# plp-cbot_2a.net
KiCad netlist of a schematic drawn in Altium Designer
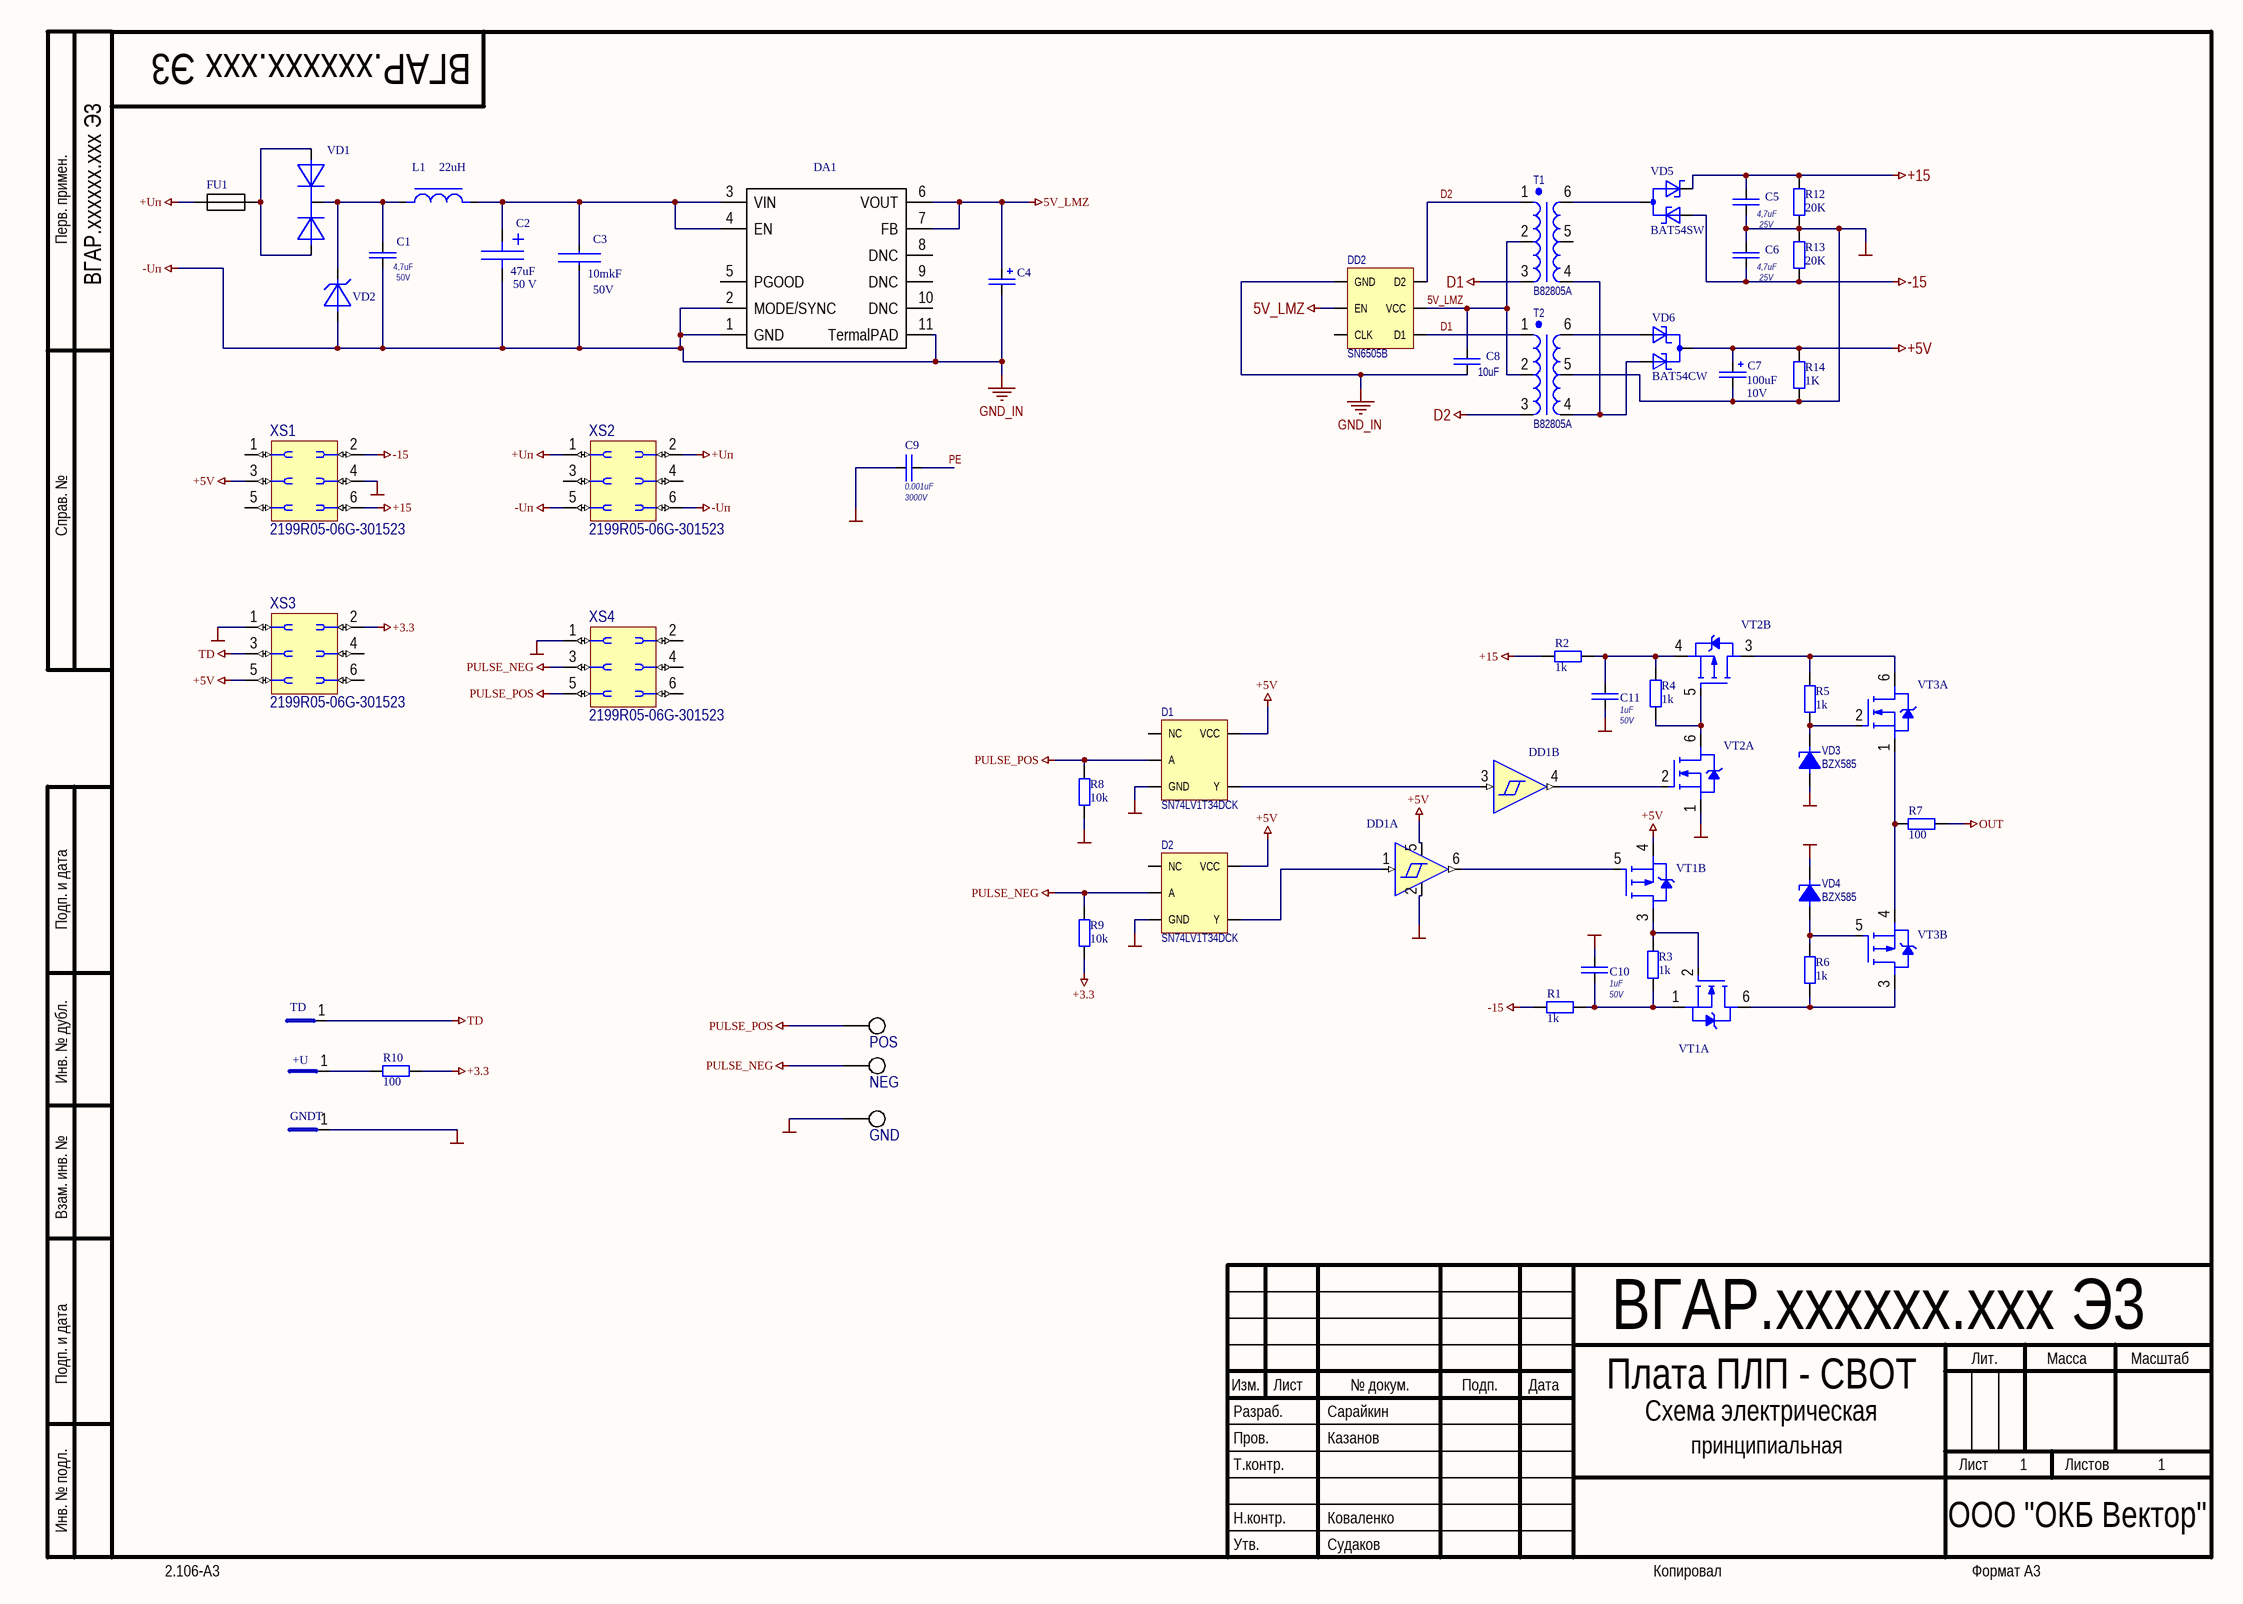
[diagram p0: plp-cbot_2a.SchDoc]

(export (version "E")
  (design (tool "Eeschema 10.0.6"))
  (components
    (comp (ref "+U")
      (value "smd_pin")
      (footprint "smd_pin")
      (libsource (lib "Board Level Debug Tools") (part "smd_pin"))
    )
    (comp (ref "C1")
      (value "4,7uF")
      (footprint "CAPC_0603(1608)X080L")
      (description "Конденсатор")
      (fields
        (field (name "MANUFACTURER") "Murata")
        (field (name "TOLERANCE") "±10%")
        (field (name "RATED DC VOLTAGE") "50V")
      )
      (libsource (lib "Chip Capacitor") (part "Capacitor Ceramic"))
    )
    (comp (ref "C2")
      (value "47uF")
      (footprint "CAPSM_D_M7878X54L")
      (description "Конденсатор")
      (fields
        (field (name "MANUFACTURER") "Panasonic")
        (field (name "TOLERANCE") "±20%")
        (field (name "RATED DC VOLTAGE") "50 V")
      )
      (libsource (lib "Panasonic Capacitor") (part "SMD 5.3XD6.3 ALUM 22uFx50V"))
    )
    (comp (ref "C3")
      (value "10mkF")
      (footprint "CAPC_1210(3225)X10L")
      (description "Capacitor Chip")
      (fields (field (name "ALTIUM_UNNAMED_1") "50V") (field (name "Comment") "CAPC_1210(3225)X10"))
      (libsource (lib "Yageo Chip Capacitor") (part "CAPC_1210(3225)X10"))
    )
    (comp (ref "C4")
      (value "~")
      (footprint "CAP_B3528X21N")
      (description "Конденсатор")
      (fields (field (name "MANUFACTURER") "Murata"))
      (libsource (lib "Chip Capacitor") (part "Capacitor Polarized"))
    )
    (comp (ref "C5")
      (value "4,7uF")
      (footprint "CAPC_0603(1608)X080L")
      (description "Конденсатор")
      (fields
        (field (name "MANUFACTURER") "Murata")
        (field (name "TOLERANCE") "±10%")
        (field (name "RATED DC VOLTAGE") "25V")
      )
      (libsource (lib "Chip Capacitor") (part "Capacitor Ceramic"))
    )
    (comp (ref "C6")
      (value "4,7uF")
      (footprint "CAPC_0603(1608)X080L")
      (description "Конденсатор")
      (fields
        (field (name "MANUFACTURER") "Murata")
        (field (name "TOLERANCE") "±10%")
        (field (name "RATED DC VOLTAGE") "25V")
      )
      (libsource (lib "Chip Capacitor") (part "Capacitor Ceramic"))
    )
    (comp (ref "C7")
      (value "100uF")
      (footprint "CAP_B3528X21N")
      (description "Конденсатор")
      (fields (field (name "MANUFACTURER") "Murata") (field (name "RATED DC VOLTAGE") "10V"))
      (libsource (lib "Chip Capacitor") (part "Capacitor Polarized"))
    )
    (comp (ref "C8")
      (value "10uF")
      (footprint "CAPC_0603(1608)X080L")
      (description "Конденсатор")
      (fields (field (name "MANUFACTURER") "Murata") (field (name "TOLERANCE") "±10%"))
      (libsource (lib "Chip Capacitor") (part "Capacitor Ceramic"))
    )
    (comp (ref "C9")
      (value "0.001uF")
      (footprint "CAPC_1812(4532)X16L")
      (description "Конденсатор")
      (fields
        (field (name "MANUFACTURER") "Murata")
        (field (name "PARTNUMBER") "0603 - 0,1 мкФ ± 10 % - 50 В - X7R")
        (field (name "RATED DC VOLTAGE") "3000V")
      )
      (libsource (lib "Chip Capacitor") (part "Capacitor Ceramic"))
    )
    (comp (ref "C10")
      (value "1uF")
      (footprint "CAPC_0603(1608)X080L")
      (description "Конденсатор")
      (fields
        (field (name "MANUFACTURER") "Murata")
        (field (name "PARTNUMBER") "GRM188R71C105KA12D - 0603 - 1 мкФ ± 10 % - 16 В - X7R")
        (field (name "RATED DC VOLTAGE") "50V")
      )
      (libsource (lib "Chip Capacitor") (part "0603 - X7R - 16V - 1uF"))
    )
    (comp (ref "C11")
      (value "1uF")
      (footprint "CAPC_0603(1608)X080L")
      (description "Конденсатор")
      (fields
        (field (name "MANUFACTURER") "Murata")
        (field (name "PARTNUMBER") "GRM188R71C105KA12D - 0603 - 1 мкФ ± 10 % - 16 В - X7R")
        (field (name "RATED DC VOLTAGE") "50V")
      )
      (libsource (lib "Chip Capacitor") (part "0603 - X7R - 16V - 1uF"))
    )
    (comp (ref "D1")
      (value "SN74LV1T34DCK")
      (footprint "SC70-5")
      (description "Single Buffer")
      (libsource (lib "ic-logic") (part "SN74LV1T34DCK"))
    )
    (comp (ref "D2")
      (value "SN74LV1T34DCK")
      (footprint "SC70-5")
      (description "Single Buffer")
      (libsource (lib "ic-logic") (part "SN74LV1T34DCK"))
    )
    (comp (ref "DA1")
      (value "LMZM23600")
      (footprint "MicroSIP")
      (description "Микросхема")
      (fields (field (name "MANUFACTURER") "Texas Instruments"))
      (libsource (lib "TI Power Mgt Switchmode Regulator") (part "LMZM23600"))
    )
    (comp (ref "DD1")
      (value "NC7WZ17P6X")
      (footprint "SC-70-6")
      (description "UHS Dual Buffer with Schmitt Trigger Inputs")
      (libsource (lib "Fairchild Logic") (part "NC7WZ17P6X"))
    )
    (comp (ref "DD2")
      (value "SN6505B")
      (footprint "SOT23-6")
      (description "Low-Noise 1-A Transformer Drivers for Isolated Power Supplies")
      (libsource (lib "ic-power-module") (part "SN6505A"))
    )
    (comp (ref "FU1")
      (value "MF-MSMF")
      (footprint "FU4532(1812)X06N")
      (description "Самовостанавливающийся предохранитель")
      (fields (field (name "MANUFACTURER") "Bourns") (field (name "PARTNUMBER") "MF-MSMF 010/60-2"))
      (libsource (lib "Bourns Chip Fuse") (part "MF-MSMF"))
    )
    (comp (ref "GND")
      (value "Testpoint_HS1mm")
      (footprint "TestPoint(1mm_HS)")
      (libsource (lib "connector") (part "Testpoint_HS1mm"))
    )
    (comp (ref "GNDT")
      (value "smd_pin")
      (footprint "smd_pin")
      (libsource (lib "Board Level Debug Tools") (part "smd_pin"))
    )
    (comp (ref "L1")
      (value "22uH")
      (footprint "CDRH4D28_INDP5050X28N")
      (fields (field (name "Comment") "CDRH4D28"))
      (libsource (lib "Sumida Power Inductor") (part "CDRH4D28"))
    )
    (comp (ref "NEG")
      (value "Testpoint_HS1mm")
      (footprint "TestPoint(1mm_HS)")
      (libsource (lib "connector") (part "Testpoint_HS1mm"))
    )
    (comp (ref "POS")
      (value "Testpoint_HS1mm")
      (footprint "TestPoint(1mm_HS)")
      (libsource (lib "connector") (part "Testpoint_HS1mm"))
    )
    (comp (ref "R1")
      (value "1k")
      (footprint "RESC1608(0603)X04L")
      (description "Резистор")
      (fields (field (name "MANUFACTURER") "Bourns") (field (name "POWER") "1/10 Вт"))
      (libsource (lib "") (part "R0603L_3"))
    )
    (comp (ref "R2")
      (value "1k")
      (footprint "RESC1608(0603)X04L")
      (description "Резистор")
      (fields (field (name "MANUFACTURER") "Bourns") (field (name "POWER") "1/10 Вт"))
      (libsource (lib "") (part "R0603L_3"))
    )
    (comp (ref "R3")
      (value "1k")
      (footprint "RESC1608(0603)X04L")
      (description "Резистор")
      (fields (field (name "MANUFACTURER") "Bourns") (field (name "POWER") "1/10 Вт"))
      (libsource (lib "") (part "R0603L_1"))
    )
    (comp (ref "R4")
      (value "1k")
      (footprint "RESC1608(0603)X04L")
      (description "Резистор")
      (fields (field (name "MANUFACTURER") "Bourns") (field (name "POWER") "1/10 Вт"))
      (libsource (lib "") (part "R0603L_1"))
    )
    (comp (ref "R5")
      (value "1k")
      (footprint "RESC1608(0603)X04L")
      (description "Резистор")
      (fields (field (name "MANUFACTURER") "Bourns") (field (name "POWER") "1/10 Вт"))
      (libsource (lib "Chip Resistor") (part "R0603L"))
    )
    (comp (ref "R6")
      (value "1k")
      (footprint "RESC1608(0603)X04L")
      (description "Резистор")
      (fields (field (name "MANUFACTURER") "Bourns") (field (name "POWER") "1/10 Вт"))
      (libsource (lib "Chip Resistor") (part "R0603L"))
    )
    (comp (ref "R7")
      (value "100")
      (footprint "RESC1608(0603)X04L")
      (description "Резистор")
      (fields (field (name "MANUFACTURER") "Bourns") (field (name "POWER") "1/10 Вт"))
      (libsource (lib "") (part "R0603L_2"))
    )
    (comp (ref "R8")
      (value "10k")
      (footprint "RESC1608(0603)X04L")
      (description "Резистор")
      (fields (field (name "MANUFACTURER") "Bourns") (field (name "POWER") "1/10 Вт"))
      (libsource (lib "") (part "R0603L_1"))
    )
    (comp (ref "R9")
      (value "10k")
      (footprint "RESC1608(0603)X04L")
      (description "Резистор")
      (fields (field (name "MANUFACTURER") "Bourns") (field (name "POWER") "1/10 Вт"))
      (libsource (lib "") (part "R0603L_1"))
    )
    (comp (ref "R10")
      (value "100")
      (footprint "RESC1608(0603)X04L")
      (description "Резистор")
      (fields (field (name "MANUFACTURER") "Bourns") (field (name "POWER") "1/10 Вт"))
      (libsource (lib "") (part "R0603L_2"))
    )
    (comp (ref "R12")
      (value "20K")
      (footprint "RESC1608(0603)X04L")
      (description "Резистор")
      (fields (field (name "MANUFACTURER") "Bourns") (field (name "POWER") "1/10 Вт"))
      (libsource (lib "") (part "R0603L_1"))
    )
    (comp (ref "R13")
      (value "20K")
      (footprint "RESC1608(0603)X04L")
      (description "Резистор")
      (fields (field (name "MANUFACTURER") "Bourns") (field (name "POWER") "1/10 Вт"))
      (libsource (lib "") (part "R0603L_1"))
    )
    (comp (ref "R14")
      (value "1K")
      (footprint "RESC1608(0603)X04L")
      (description "Резистор")
      (fields (field (name "MANUFACTURER") "Bourns") (field (name "POWER") "1/10 Вт"))
      (libsource (lib "") (part "R0603L_1"))
    )
    (comp (ref "T1")
      (value "B82805A")
      (footprint "B82805A")
      (description "SMT Push-Pull Transformers")
      (libsource (lib "transformer") (part "B82805A"))
    )
    (comp (ref "T2")
      (value "B82805A")
      (footprint "B82805A")
      (description "SMT Push-Pull Transformers")
      (libsource (lib "transformer") (part "B82805A"))
    )
    (comp (ref "TD")
      (value "smd_pin")
      (footprint "smd_pin")
      (libsource (lib "Board Level Debug Tools") (part "smd_pin"))
    )
    (comp (ref "VD1")
      (value "BAV70W")
      (footprint "SC-70")
      (description "Сборка диодная")
      (fields (field (name "MANUFACTURER") "NXP"))
      (libsource (lib "NXP Diodes") (part "BAV70W"))
    )
    (comp (ref "VD2")
      (value "SMBJ33A")
      (footprint "SMB")
      (description "TVS Диод")
      (fields
        (field (name "REPLACEMENTPART1PARTNUMBER") "PTVS33VP1UP")
        (field (name "MANUFACTURER") "ST Microelectronics")
      )
      (libsource (lib "ST Protection Diodes") (part "SMBJ33A"))
    )
    (comp (ref "VD3")
      (value "BZX585")
      (footprint "DIODE: SOD523")
      (description "Voltage regulator diodes")
      (libsource (lib "diode") (part "BZX585"))
    )
    (comp (ref "VD4")
      (value "BZX585")
      (footprint "DIODE: SOD523")
      (description "Voltage regulator diodes")
      (libsource (lib "diode") (part "BZX585"))
    )
    (comp (ref "VD5")
      (value "BAT54SW")
      (footprint "SC-70")
      (description "Сборка диодная")
      (fields (field (name "MANUFACTURER") "NXP") (field (name "REPLACEMENTPART1PARTNUMBER") "BAT54SWT1G"))
      (libsource (lib "NXP Diodes") (part "BAT54SW"))
    )
    (comp (ref "VD6")
      (value "BAT54CW")
      (footprint "SC-70")
      (description "Сборка диодная")
      (fields (field (name "MANUFACTURER") "NXP") (field (name "REPLACEMENTPART1PARTNUMBER") "BAT54CWT1G"))
      (libsource (lib "NXP Diodes") (part "BAT54CW"))
    )
    (comp (ref "VT1")
      (value "NX3008CBKS")
      (footprint "SC-70-6")
      (description "Сборка транзисторная")
      (fields (field (name "MANUFACTURER") "Fairchild Semiconductor") (field (name "PARTNUMBER") "BSS84AKS"))
      (libsource (lib "NXP Transistors") (part "NX3008CBKS"))
    )
    (comp (ref "VT2")
      (value "NX3008CBKS")
      (footprint "SC-70-6")
      (description "Сборка транзисторная")
      (fields (field (name "MANUFACTURER") "Fairchild Semiconductor") (field (name "PARTNUMBER") "BSS84AKS"))
      (libsource (lib "NXP Transistors") (part "NX3008CBKS"))
    )
    (comp (ref "VT3")
      (value "NX3008CBKS")
      (footprint "SC-70-6")
      (description "Сборка транзисторная")
      (fields (field (name "MANUFACTURER") "Fairchild Semiconductor") (field (name "PARTNUMBER") "BSS84AKS"))
      (libsource (lib "NXP Transistors") (part "NX3008CBKS"))
    )
    (comp (ref "XS1")
      (value "2199R05-06G-301523")
      (footprint "CON: PLL-6(2x3R1.27female)")
      (description "Step 1.27")
      (libsource (lib "connector") (part "2199R05-06G-301523In"))
    )
    (comp (ref "XS2")
      (value "2199R05-06G-301523")
      (footprint "CON: PLL-6(2x3R1.27female)")
      (description "Step 1.27")
      (libsource (lib "connector") (part "2199R05-06G-301523In"))
    )
    (comp (ref "XS3")
      (value "2199R05-06G-301523")
      (footprint "CON: PLL-6(2x3R1.27female)")
      (description "Step 1.27")
      (libsource (lib "connector") (part "2199R05-06G-301523In"))
    )
    (comp (ref "XS4")
      (value "2199R05-06G-301523")
      (footprint "CON: PLL-6(2x3R1.27female)")
      (description "Step 1.27")
      (libsource (lib "connector") (part "2199R05-06G-301523In"))
    )
  )
  (nets
    (net (code "1") (name "+3.3") (class "Default")
      (node (ref "R10") (pin "2") (pinfunction "2_2") (pintype "passive"))
      (node (ref "R9") (pin "1") (pinfunction "1_1") (pintype "passive"))
      (node (ref "XS3") (pin "2") (pinfunction "2_2") (pintype "bidirectional"))
    )
    (net (code "2") (name "+5V") (class "Default")
      (node (ref "C7") (pin "1") (pinfunction "1_1") (pintype "passive"))
      (node (ref "D1") (pin "5") (pinfunction "VCC_5") (pintype "passive"))
      (node (ref "D2") (pin "5") (pinfunction "VCC_5") (pintype "passive"))
      (node (ref "DD1") (pin "5") (pinfunction "Vdd_5") (pintype "passive"))
      (node (ref "R14") (pin "2") (pinfunction "2_2") (pintype "passive"))
      (node (ref "VD6") (pin "3") (pinfunction "OC_3") (pintype "passive"))
      (node (ref "VT1") (pin "4") (pinfunction "S2_4") (pintype "passive"))
      (node (ref "XS1") (pin "3") (pinfunction "3_3") (pintype "bidirectional"))
      (node (ref "XS3") (pin "5") (pinfunction "5_5") (pintype "bidirectional"))
    )
    (net (code "3") (name "+15") (class "Default")
      (node (ref "C5") (pin "2") (pinfunction "2_2") (pintype "passive"))
      (node (ref "R12") (pin "2") (pinfunction "2_2") (pintype "passive"))
      (node (ref "R2") (pin "2") (pinfunction "2_2") (pintype "passive"))
      (node (ref "VD5") (pin "2") (pinfunction "C_2") (pintype "passive"))
      (node (ref "XS1") (pin "6") (pinfunction "6_6") (pintype "bidirectional"))
    )
    (net (code "4") (name "+Uп") (class "Default")
      (node (ref "FU1") (pin "1") (pinfunction "1_1") (pintype "passive"))
      (node (ref "XS2") (pin "1") (pinfunction "1_1") (pintype "bidirectional"))
      (node (ref "XS2") (pin "2") (pinfunction "2_2") (pintype "bidirectional"))
    )
    (net (code "5") (name "-15") (class "Default")
      (node (ref "C6") (pin "1") (pinfunction "1_1") (pintype "passive"))
      (node (ref "R1") (pin "2") (pinfunction "2_2") (pintype "passive"))
      (node (ref "R13") (pin "1") (pinfunction "1_1") (pintype "passive"))
      (node (ref "VD5") (pin "1") (pinfunction "A_1") (pintype "passive"))
      (node (ref "XS1") (pin "2") (pinfunction "2_2") (pintype "bidirectional"))
    )
    (net (code "6") (name "-Uп") (class "Default")
      (node (ref "C1") (pin "1") (pinfunction "1_1") (pintype "passive"))
      (node (ref "C2") (pin "2") (pinfunction "2_2") (pintype "passive"))
      (node (ref "C3") (pin "1") (pinfunction "1_1") (pintype "passive"))
      (node (ref "C4") (pin "2") (pinfunction "2_2") (pintype "passive"))
      (node (ref "C8") (pin "1") (pinfunction "1_1") (pintype "passive"))
      (node (ref "DA1") (pin "1") (pinfunction "GND_1") (pintype "passive"))
      (node (ref "DA1") (pin "11") (pinfunction "TermalPAD_11") (pintype "passive"))
      (node (ref "DA1") (pin "2") (pinfunction "MODE/SYNC_2") (pintype "passive"))
      (node (ref "DD2") (pin "4") (pinfunction "GND_4") (pintype "passive"))
      (node (ref "VD2") (pin "2") (pinfunction "A_2") (pintype "passive"))
      (node (ref "XS2") (pin "5") (pinfunction "5_5") (pintype "bidirectional"))
      (node (ref "XS2") (pin "6") (pinfunction "6_6") (pintype "bidirectional"))
    )
    (net (code "7") (name "/PE") (class "Default")
      (node (ref "C9") (pin "2") (pinfunction "2_2") (pintype "passive"))
    )
    (net (code "8") (name "5V_LMZ") (class "Default")
      (node (ref "C4") (pin "1") (pinfunction "1_1") (pintype "passive"))
      (node (ref "C8") (pin "2") (pinfunction "2_2") (pintype "passive"))
      (node (ref "DA1") (pin "6") (pinfunction "VOUT_6") (pintype "passive"))
      (node (ref "DA1") (pin "7") (pinfunction "FB_7") (pintype "passive"))
      (node (ref "DD2") (pin "2") (pinfunction "VCC_2") (pintype "passive"))
      (node (ref "DD2") (pin "5") (pinfunction "EN_5") (pintype "passive"))
      (node (ref "T1") (pin "2") (pinfunction "2_2") (pintype "passive"))
      (node (ref "T2") (pin "2") (pinfunction "2_2") (pintype "passive"))
    )
    (net (code "9") (name "D1") (class "Default")
      (node (ref "DD2") (pin "1") (pinfunction "D1_1") (pintype "passive"))
      (node (ref "T1") (pin "3") (pinfunction "3_3") (pintype "passive"))
      (node (ref "T2") (pin "1") (pinfunction "1_1") (pintype "passive"))
    )
    (net (code "10") (name "D2") (class "Default")
      (node (ref "DD2") (pin "3") (pinfunction "D2_3") (pintype "passive"))
      (node (ref "T1") (pin "1") (pinfunction "1_1") (pintype "passive"))
      (node (ref "T2") (pin "3") (pinfunction "3_3") (pintype "passive"))
    )
    (net (code "11") (name "GND") (class "Default")
      (node (ref "C10") (pin "2") (pinfunction "2_2") (pintype "passive"))
      (node (ref "C11") (pin "1") (pinfunction "1_1") (pintype "passive"))
      (node (ref "C5") (pin "1") (pinfunction "1_1") (pintype "passive"))
      (node (ref "C6") (pin "2") (pinfunction "2_2") (pintype "passive"))
      (node (ref "C7") (pin "2") (pinfunction "2_2") (pintype "passive"))
      (node (ref "C9") (pin "1") (pinfunction "1_1") (pintype "passive"))
      (node (ref "D1") (pin "3") (pinfunction "GND_3") (pintype "passive"))
      (node (ref "D2") (pin "3") (pinfunction "GND_3") (pintype "passive"))
      (node (ref "DD1") (pin "2") (pinfunction "GND_2") (pintype "passive"))
      (node (ref "GND") (pin "1") (pinfunction "1_1") (pintype "passive"))
      (node (ref "GNDT") (pin "1") (pinfunction "0_1") (pintype "passive"))
      (node (ref "R12") (pin "1") (pinfunction "1_1") (pintype "passive"))
      (node (ref "R13") (pin "2") (pinfunction "2_2") (pintype "passive"))
      (node (ref "R14") (pin "1") (pinfunction "1_1") (pintype "passive"))
      (node (ref "R8") (pin "1") (pinfunction "1_1") (pintype "passive"))
      (node (ref "T2") (pin "5") (pinfunction "5_5") (pintype "passive"))
      (node (ref "VD3") (pin "1") (pinfunction "2_1") (pintype "passive"))
      (node (ref "VD4") (pin "2") (pinfunction "1_2") (pintype "passive"))
      (node (ref "VT2") (pin "1") (pinfunction "S1_1") (pintype "passive"))
      (node (ref "XS1") (pin "4") (pinfunction "4_4") (pintype "bidirectional"))
      (node (ref "XS3") (pin "1") (pinfunction "1_1") (pintype "bidirectional"))
      (node (ref "XS4") (pin "1") (pinfunction "1_1") (pintype "bidirectional"))
    )
    (net (code "12") (name "Net-(+U-0)") (class "Default")
      (node (ref "+U") (pin "1") (pinfunction "0_1") (pintype "passive"))
      (node (ref "R10") (pin "1") (pinfunction "1_1") (pintype "passive"))
    )
    (net (code "13") (name "Net-(D1-Y)") (class "Default")
      (node (ref "D1") (pin "4") (pinfunction "Y_4") (pintype "passive"))
      (node (ref "DD1") (pin "3") (pinfunction "A2_3") (pintype "input"))
    )
    (net (code "14") (name "Net-(D2-Y)") (class "Default")
      (node (ref "D2") (pin "4") (pinfunction "Y_4") (pintype "passive"))
      (node (ref "DD1") (pin "1") (pinfunction "A1_1") (pintype "input"))
    )
    (net (code "15") (name "Net-(DA1-EN)") (class "Default")
      (node (ref "C2") (pin "1") (pinfunction "1_1") (pintype "passive"))
      (node (ref "C3") (pin "2") (pinfunction "2_2") (pintype "passive"))
      (node (ref "DA1") (pin "3") (pinfunction "VIN_3") (pintype "passive"))
      (node (ref "DA1") (pin "4") (pinfunction "EN_4") (pintype "passive"))
      (node (ref "L1") (pin "2") (pinfunction "2_2") (pintype "passive"))
    )
    (net (code "16") (name "Net-(DD1A-Y1)") (class "Default")
      (node (ref "DD1") (pin "6") (pinfunction "Y1_6") (pintype "output"))
      (node (ref "VT1") (pin "5") (pinfunction "G2_5") (pintype "passive"))
    )
    (net (code "17") (name "Net-(DD1B-Y2)") (class "Default")
      (node (ref "DD1") (pin "4") (pinfunction "Y2_4") (pintype "output"))
      (node (ref "VT2") (pin "2") (pinfunction "G1_2") (pintype "passive"))
    )
    (net (code "18") (name "Net-(FU1-Pad2)") (class "Default")
      (node (ref "FU1") (pin "2") (pinfunction "2_2") (pintype "passive"))
      (node (ref "VD1") (pin "1") (pinfunction "A_1") (pintype "passive"))
      (node (ref "VD1") (pin "2") (pinfunction "A_2") (pintype "passive"))
    )
    (net (code "19") (name "Net-(T1-Pad4)") (class "Default")
      (node (ref "T1") (pin "4") (pinfunction "4_4") (pintype "passive"))
      (node (ref "T2") (pin "4") (pinfunction "4_4") (pintype "passive"))
      (node (ref "VD6") (pin "2") (pinfunction "A_2") (pintype "passive"))
    )
    (net (code "20") (name "Net-(T2-Pad6)") (class "Default")
      (node (ref "T2") (pin "6") (pinfunction "6_6") (pintype "passive"))
      (node (ref "VD6") (pin "1") (pinfunction "A_1") (pintype "passive"))
    )
    (net (code "21") (name "Net-(VD1-OC)") (class "Default")
      (node (ref "C1") (pin "2") (pinfunction "2_2") (pintype "passive"))
      (node (ref "L1") (pin "1") (pinfunction "1_1") (pintype "passive"))
      (node (ref "VD1") (pin "3") (pinfunction "OC_3") (pintype "passive"))
      (node (ref "VD2") (pin "1") (pinfunction "C_1") (pintype "passive"))
    )
    (net (code "22") (name "Net-(VD3-1)") (class "Default")
      (node (ref "R5") (pin "2") (pinfunction "2_2") (pintype "passive"))
      (node (ref "VD3") (pin "2") (pinfunction "1_2") (pintype "passive"))
      (node (ref "VT3") (pin "2") (pinfunction "G1_2") (pintype "passive"))
    )
    (net (code "23") (name "Net-(VD4-2)") (class "Default")
      (node (ref "R6") (pin "1") (pinfunction "1_1") (pintype "passive"))
      (node (ref "VD4") (pin "1") (pinfunction "2_1") (pintype "passive"))
      (node (ref "VT3") (pin "5") (pinfunction "G2_5") (pintype "passive"))
    )
    (net (code "24") (name "Net-(VD5-OAC)") (class "Default")
      (node (ref "T1") (pin "6") (pinfunction "6_6") (pintype "passive"))
      (node (ref "VD5") (pin "3") (pinfunction "OAC_3") (pintype "passive"))
    )
    (net (code "25") (name "Net-(VT1A-D1)") (class "Default")
      (node (ref "R6") (pin "2") (pinfunction "2_2") (pintype "passive"))
      (node (ref "VT1") (pin "6") (pinfunction "D1_6") (pintype "passive"))
      (node (ref "VT3") (pin "3") (pinfunction "D2_3") (pintype "passive"))
    )
    (net (code "26") (name "Net-(VT1A-G1)") (class "Default")
      (node (ref "R3") (pin "2") (pinfunction "2_2") (pintype "passive"))
      (node (ref "VT1") (pin "2") (pinfunction "G1_2") (pintype "passive"))
      (node (ref "VT1") (pin "3") (pinfunction "D2_3") (pintype "passive"))
    )
    (net (code "27") (name "Net-(VT1A-S1)") (class "Default")
      (node (ref "C10") (pin "1") (pinfunction "1_1") (pintype "passive"))
      (node (ref "R1") (pin "1") (pinfunction "1_1") (pintype "passive"))
      (node (ref "R3") (pin "1") (pinfunction "1_1") (pintype "passive"))
      (node (ref "VT1") (pin "1") (pinfunction "S1_1") (pintype "passive"))
    )
    (net (code "28") (name "Net-(VT2A-D1)") (class "Default")
      (node (ref "R4") (pin "1") (pinfunction "1_1") (pintype "passive"))
      (node (ref "VT2") (pin "5") (pinfunction "G2_5") (pintype "passive"))
      (node (ref "VT2") (pin "6") (pinfunction "D1_6") (pintype "passive"))
    )
    (net (code "29") (name "Net-(VT2B-D2)") (class "Default")
      (node (ref "R5") (pin "1") (pinfunction "1_1") (pintype "passive"))
      (node (ref "VT2") (pin "3") (pinfunction "D2_3") (pintype "passive"))
      (node (ref "VT3") (pin "6") (pinfunction "D1_6") (pintype "passive"))
    )
    (net (code "30") (name "Net-(VT2B-S2)") (class "Default")
      (node (ref "C11") (pin "2") (pinfunction "2_2") (pintype "passive"))
      (node (ref "R2") (pin "1") (pinfunction "1_1") (pintype "passive"))
      (node (ref "R4") (pin "2") (pinfunction "2_2") (pintype "passive"))
      (node (ref "VT2") (pin "4") (pinfunction "S2_4") (pintype "passive"))
    )
    (net (code "31") (name "Net-(VT3A-S1)") (class "Default")
      (node (ref "R7") (pin "1") (pinfunction "1_1") (pintype "passive"))
      (node (ref "VT3") (pin "1") (pinfunction "S1_1") (pintype "passive"))
      (node (ref "VT3") (pin "4") (pinfunction "S2_4") (pintype "passive"))
    )
    (net (code "32") (name "OUT") (class "Default")
      (node (ref "R7") (pin "2") (pinfunction "2_2") (pintype "passive"))
    )
    (net (code "33") (name "PULSE_NEG") (class "Default")
      (node (ref "D2") (pin "2") (pinfunction "A_2") (pintype "passive"))
      (node (ref "NEG") (pin "1") (pinfunction "1_1") (pintype "passive"))
      (node (ref "R9") (pin "2") (pinfunction "2_2") (pintype "passive"))
      (node (ref "XS4") (pin "3") (pinfunction "3_3") (pintype "bidirectional"))
    )
    (net (code "34") (name "PULSE_POS") (class "Default")
      (node (ref "D1") (pin "2") (pinfunction "A_2") (pintype "passive"))
      (node (ref "POS") (pin "1") (pinfunction "1_1") (pintype "passive"))
      (node (ref "R8") (pin "2") (pinfunction "2_2") (pintype "passive"))
      (node (ref "XS4") (pin "5") (pinfunction "5_5") (pintype "bidirectional"))
    )
    (net (code "35") (name "TD") (class "Default")
      (node (ref "TD") (pin "1") (pinfunction "0_1") (pintype "passive"))
      (node (ref "XS3") (pin "3") (pinfunction "3_3") (pintype "bidirectional"))
    )
    (net (code "36") (name "unconnected-(D1-NC-Pad1)") (class "Default")
      (node (ref "D1") (pin "1") (pinfunction "NC_1") (pintype "passive"))
    )
    (net (code "37") (name "unconnected-(D2-NC-Pad1)") (class "Default")
      (node (ref "D2") (pin "1") (pinfunction "NC_1") (pintype "passive"))
    )
    (net (code "38") (name "unconnected-(DA1-DNC-Pad8)") (class "Default")
      (node (ref "DA1") (pin "8") (pinfunction "DNC_8") (pintype "passive"))
    )
    (net (code "39") (name "unconnected-(DA1-DNC-Pad9)") (class "Default")
      (node (ref "DA1") (pin "9") (pinfunction "DNC_9") (pintype "passive"))
    )
    (net (code "40") (name "unconnected-(DA1-DNC-Pad10)") (class "Default")
      (node (ref "DA1") (pin "10") (pinfunction "DNC_10") (pintype "passive"))
    )
    (net (code "41") (name "unconnected-(DA1-PGOOD-Pad5)") (class "Default")
      (node (ref "DA1") (pin "5") (pinfunction "PGOOD_5") (pintype "passive"))
    )
    (net (code "42") (name "unconnected-(DD2-CLK-Pad6)") (class "Default")
      (node (ref "DD2") (pin "6") (pinfunction "CLK_6") (pintype "passive"))
    )
    (net (code "43") (name "unconnected-(T1-Pad5)") (class "Default")
      (node (ref "T1") (pin "5") (pinfunction "5_5") (pintype "passive"))
    )
    (net (code "44") (name "unconnected-(XS1-Pad1)") (class "Default")
      (node (ref "XS1") (pin "1") (pinfunction "1_1") (pintype "bidirectional"))
    )
    (net (code "45") (name "unconnected-(XS1-Pad5)") (class "Default")
      (node (ref "XS1") (pin "5") (pinfunction "5_5") (pintype "bidirectional"))
    )
    (net (code "46") (name "unconnected-(XS2-Pad3)") (class "Default")
      (node (ref "XS2") (pin "3") (pinfunction "3_3") (pintype "bidirectional"))
    )
    (net (code "47") (name "unconnected-(XS2-Pad4)") (class "Default")
      (node (ref "XS2") (pin "4") (pinfunction "4_4") (pintype "bidirectional"))
    )
    (net (code "48") (name "unconnected-(XS3-Pad4)") (class "Default")
      (node (ref "XS3") (pin "4") (pinfunction "4_4") (pintype "bidirectional"))
    )
    (net (code "49") (name "unconnected-(XS3-Pad6)") (class "Default")
      (node (ref "XS3") (pin "6") (pinfunction "6_6") (pintype "bidirectional"))
    )
    (net (code "50") (name "unconnected-(XS4-Pad2)") (class "Default")
      (node (ref "XS4") (pin "2") (pinfunction "2_2") (pintype "bidirectional"))
    )
    (net (code "51") (name "unconnected-(XS4-Pad4)") (class "Default")
      (node (ref "XS4") (pin "4") (pinfunction "4_4") (pintype "bidirectional"))
    )
    (net (code "52") (name "unconnected-(XS4-Pad6)") (class "Default")
      (node (ref "XS4") (pin "6") (pinfunction "6_6") (pintype "bidirectional"))
    )
  )
)
